# FTDIBreakoutAdapter.net
KiCad netlist of a schematic drawn in EAGLE
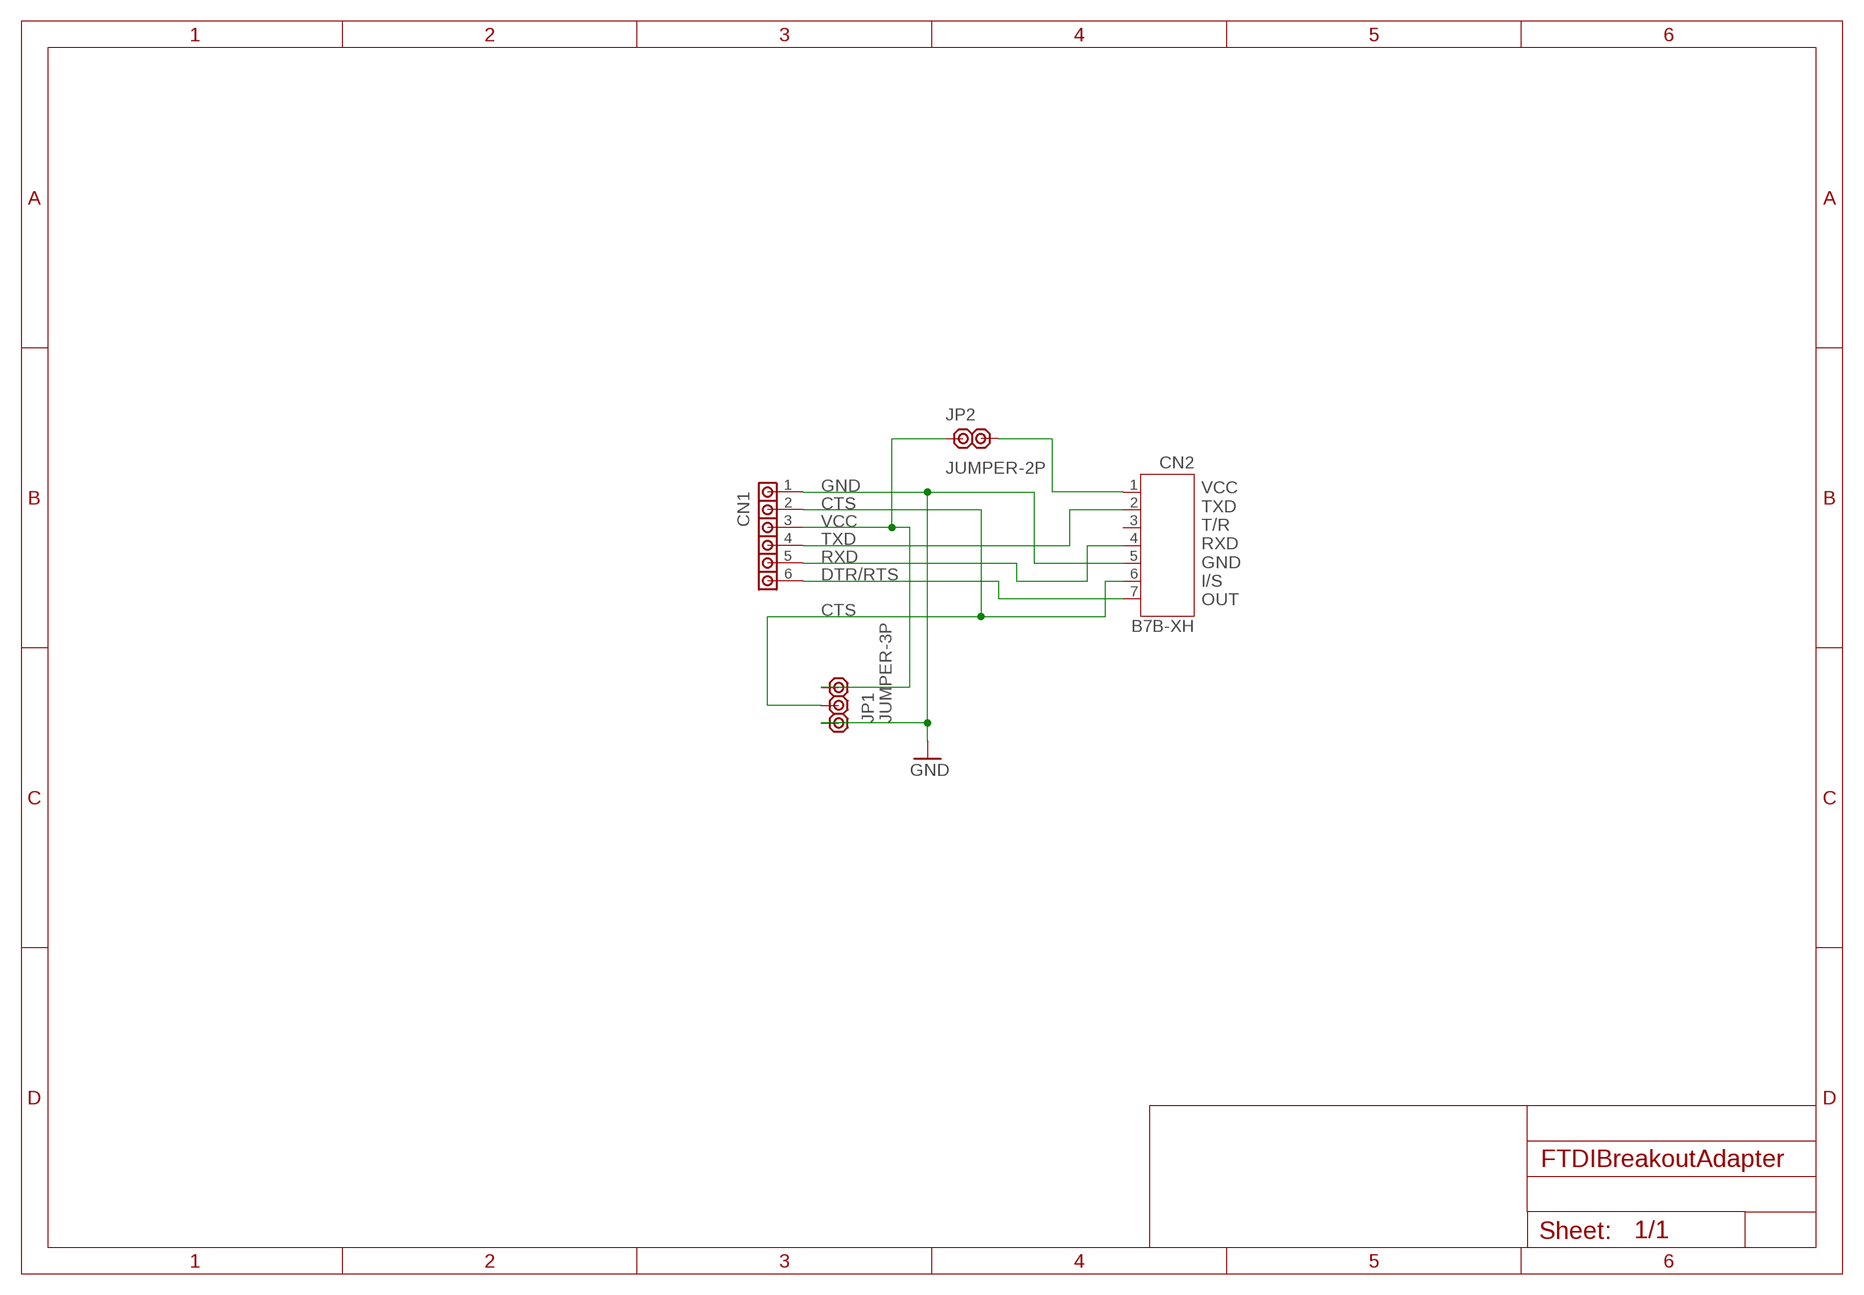
[diagram p0: schematic, sheet 1]

(export (version "E")
  (design (tool "Eeschema 10.0.6"))
  (components
    (comp (ref "CN1")
      (value "H6-2.54-90D-MALE")
      (footprint "eagle-import:H6-2.54-90D-MALE")
      (libsource (lib "eagle-import") (part "H6-2.54-90D-MALE"))
    )
    (comp (ref "CN2")
      (value "B7B-XH")
      (footprint "eagle-import:B7B-XH")
      (libsource (lib "eagle-import") (part "B7B-XH"))
    )
    (comp (ref "JP1")
      (value "JUMPER-3P")
      (footprint "eagle-import:JUMPER-3P")
      (libsource (lib "eagle-import") (part "JUMPER-3P"))
    )
    (comp (ref "JP2")
      (value "JUMPER-2P")
      (footprint "eagle-import:JUMPER-2P")
      (libsource (lib "eagle-import") (part "JUMPER-2P"))
    )
  )
  (nets
    (net (code "1") (name "/CTS") (class "Default")
      (node (ref "CN1") (pin "2") (pinfunction "2_2") (pintype "passive"))
      (node (ref "CN2") (pin "6") (pinfunction "6_6") (pintype "passive"))
      (node (ref "JP1") (pin "2") (pinfunction "P$2_2") (pintype "bidirectional"))
    )
    (net (code "2") (name "/DTR{slash}RTS") (class "Default")
      (node (ref "CN1") (pin "6") (pinfunction "6_6") (pintype "passive"))
      (node (ref "CN2") (pin "7") (pinfunction "7_7") (pintype "passive"))
    )
    (net (code "3") (name "/RXD") (class "Default")
      (node (ref "CN1") (pin "5") (pinfunction "5_5") (pintype "passive"))
      (node (ref "CN2") (pin "4") (pinfunction "4_4") (pintype "passive"))
    )
    (net (code "4") (name "/TXD") (class "Default")
      (node (ref "CN1") (pin "4") (pinfunction "4_4") (pintype "passive"))
      (node (ref "CN2") (pin "2") (pinfunction "2_2") (pintype "passive"))
    )
    (net (code "5") (name "/VCC") (class "Default")
      (node (ref "CN1") (pin "3") (pinfunction "3_3") (pintype "passive"))
      (node (ref "JP1") (pin "1") (pinfunction "P$1_1") (pintype "bidirectional"))
      (node (ref "JP2") (pin "1") (pinfunction "P$2_1") (pintype "bidirectional"))
    )
    (net (code "6") (name "GND") (class "Default")
      (node (ref "CN1") (pin "1") (pinfunction "1_1") (pintype "passive"))
      (node (ref "CN2") (pin "5") (pinfunction "5_5") (pintype "passive"))
      (node (ref "JP1") (pin "3") (pinfunction "P$3_3") (pintype "bidirectional"))
    )
    (net (code "7") (name "Net-(JP2-P$1)") (class "Default")
      (node (ref "CN2") (pin "1") (pinfunction "1_1") (pintype "passive"))
      (node (ref "JP2") (pin "2") (pinfunction "P$1_2") (pintype "bidirectional"))
    )
    (net (code "8") (name "unconnected-(CN2-Pad3)") (class "Default")
      (node (ref "CN2") (pin "3") (pinfunction "3_3") (pintype "passive"))
    )
  )
)
